# Sensors.net
KiCad netlist of a schematic drawn in Altium Designer
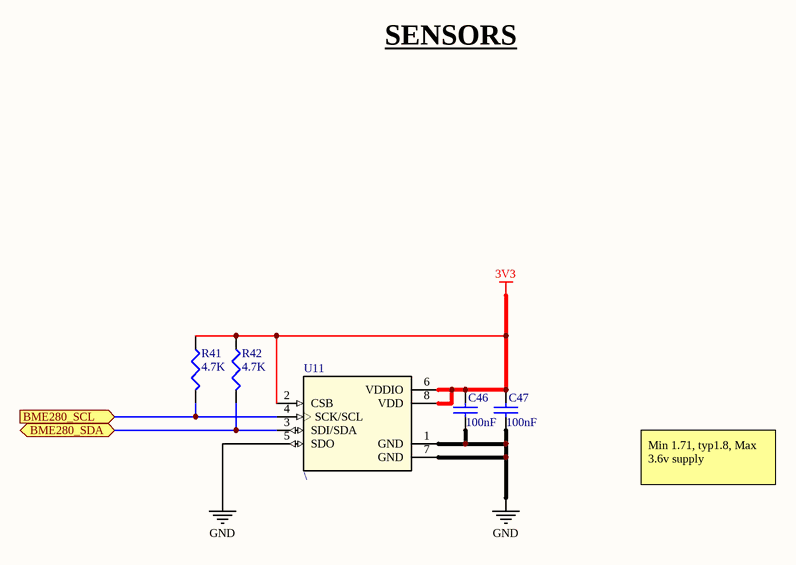
[diagram p0: Sensors.SchDoc]

(export (version "E")
  (design (tool "Eeschema 10.0.6"))
  (components
    (comp (ref "C46")
      (value "Capacitor")
      (footprint "CAP0402")
      (fields
        (field (name "MANUFACTURER") "TDK")
        (field (name "MANUFACTURER PART NUMBER") "CGA2B3X7R1H104K050BB")
        (field (name "CAPACITANCE") "100nF")
        (field (name "TOLERANCE") "10%")
      )
      (libsource (lib "BPL-ShematicLibrary") (part "Capacitor"))
    )
    (comp (ref "C47")
      (value "Capacitor")
      (footprint "CAP0402")
      (fields
        (field (name "MANUFACTURER") "TDK")
        (field (name "MANUFACTURER PART NUMBER") "CGA2B3X7R1H104K050BB")
        (field (name "CAPACITANCE") "100nF")
        (field (name "TOLERANCE") "10%")
      )
      (libsource (lib "BPL-ShematicLibrary") (part "Capacitor"))
    )
    (comp (ref "R41")
      (value "4.7K")
      (footprint "RES0402")
      (description "Resistor")
      (fields
        (field (name "MANUFACTURER") "Yageo")
        (field (name "MANUFACTURER PART NUMBER") "RC0402FR-074K7L")
      )
      (libsource (lib "BPL-ShematicLibrary") (part "Resistor"))
    )
    (comp (ref "R42")
      (value "4.7K")
      (footprint "RES0402")
      (description "Resistor")
      (fields
        (field (name "MANUFACTURER") "Yageo")
        (field (name "MANUFACTURER PART NUMBER") "RC0402FR-074K7L")
      )
      (libsource (lib "BPL-ShematicLibrary") (part "Resistor"))
    )
    (comp (ref "U11")
      (value "\\")
      (footprint "BME280")
      (description "Bosch Temp, Hum, Abs Pressure Environmental Sensor")
      (libsource (lib "BPL-ShematicLibrary") (part "BME280"))
    )
  )
  (nets
    (net (code "1") (name "/BME280_SCL") (class "Default")
      (node (ref "R41") (pin "2") (pinfunction "2_2") (pintype "passive"))
      (node (ref "U11") (pin "4") (pinfunction "SCK/SCL_4") (pintype "input"))
    )
    (net (code "2") (name "/BME280_SDA") (class "Default")
      (node (ref "R42") (pin "2") (pinfunction "2_2") (pintype "passive"))
      (node (ref "U11") (pin "3") (pinfunction "SDI/SDA_3") (pintype "bidirectional"))
    )
    (net (code "3") (name "3V3") (class "Default")
      (node (ref "C46") (pin "1") (pinfunction "1_1") (pintype "passive"))
      (node (ref "C47") (pin "1") (pinfunction "1_1") (pintype "passive"))
      (node (ref "R41") (pin "1") (pinfunction "1_1") (pintype "passive"))
      (node (ref "R42") (pin "1") (pinfunction "1_1") (pintype "passive"))
      (node (ref "U11") (pin "2") (pinfunction "CSB_2") (pintype "input"))
      (node (ref "U11") (pin "6") (pinfunction "VDDIO_6") (pintype "power_in"))
      (node (ref "U11") (pin "8") (pinfunction "VDD_8") (pintype "power_in"))
    )
    (net (code "4") (name "GND") (class "Default")
      (node (ref "C46") (pin "2") (pinfunction "2_2") (pintype "passive"))
      (node (ref "C47") (pin "2") (pinfunction "2_2") (pintype "passive"))
      (node (ref "U11") (pin "1") (pinfunction "GND_1") (pintype "power_in"))
      (node (ref "U11") (pin "5") (pinfunction "SDO_5") (pintype "bidirectional"))
      (node (ref "U11") (pin "7") (pinfunction "GND_7") (pintype "power_in"))
    )
  )
)
